# Battery_Gate_Driver.net
KiCad netlist of a schematic drawn in Altium Designer
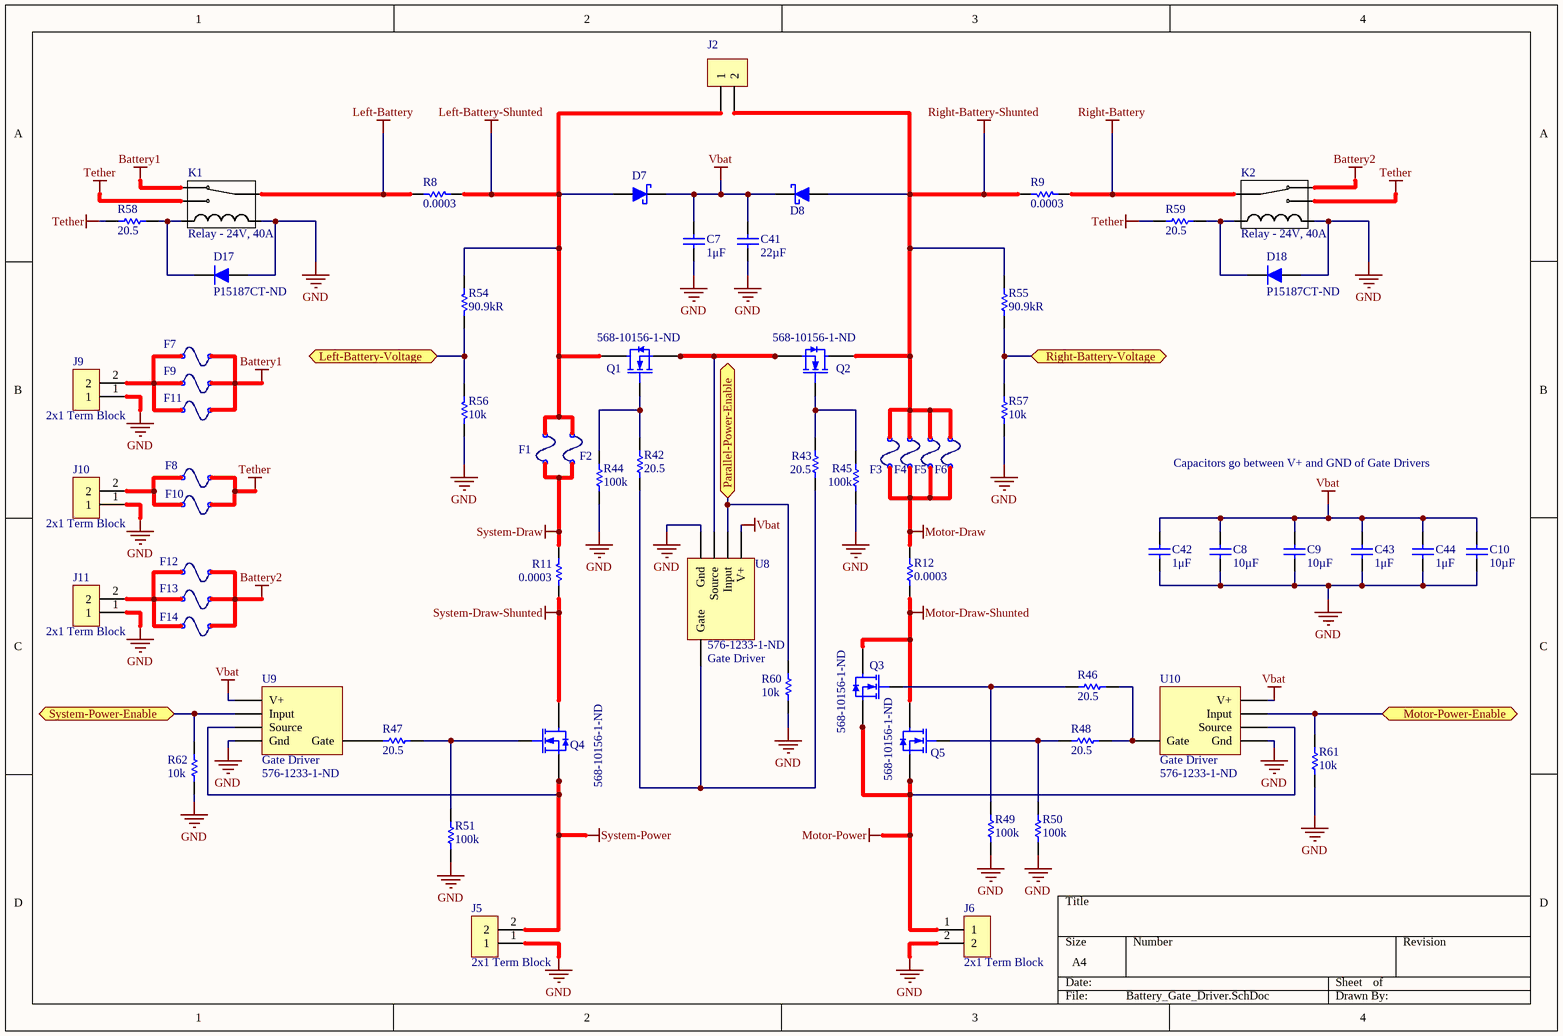
[diagram p0: Battery_Gate_Driver.SchDoc]

(export (version "E")
  (design (tool "Eeschema 10.0.6"))
  (components
    (comp (ref "C7")
      (value "1μF")
      (footprint "CAPC1608N(0603\")")
      (description "Capacitor, Ceramic, 50V, +/- 10%, 0603 SMD, X5R")
      (fields (field (name "CREATED BY") "Lyden Smith"))
      (libsource (lib "AUVic_Integrated_Library_Capacitors") (part "1uF 50V 0603 SMD, Ceramic"))
    )
    (comp (ref "C8")
      (value "10µF")
      (footprint "CAPC3216N(1206\")")
      (description "Capacitor, Ceramic, 50V, +/- 10%, 1206 SMD, X5R")
      (fields (field (name "PUBLISHER") "AUVic"))
      (libsource (lib "AUVic_Integrated_Library_Capacitors") (part "10uF 50V 1206 SMD, Ceramic"))
    )
    (comp (ref "C9")
      (value "10µF")
      (footprint "CAPC3216N(1206\")")
      (description "Capacitor, Ceramic, 50V, +/- 10%, 1206 SMD, X5R")
      (fields (field (name "PUBLISHER") "AUVic"))
      (libsource (lib "AUVic_Integrated_Library_Capacitors") (part "10uF 50V 1206 SMD, Ceramic"))
    )
    (comp (ref "C10")
      (value "10µF")
      (footprint "CAPC3216N(1206\")")
      (description "Capacitor, Ceramic, 50V, +/- 10%, 1206 SMD, X5R")
      (fields (field (name "PUBLISHER") "AUVic"))
      (libsource (lib "AUVic_Integrated_Library_Capacitors") (part "10uF 50V 1206 SMD, Ceramic"))
    )
    (comp (ref "C41")
      (value "22µF")
      (footprint "CAPC2012N(0805\")")
      (description "Capacitor, Ceramic, 35V, +/- 20%, 0805 SMD, X5R")
      (fields (field (name "PUBLISHER") "AUVic"))
      (libsource (lib "AUVic_Integrated_Library_Capacitors") (part "22uF 35V 0805 SMD, Ceramic"))
    )
    (comp (ref "C42")
      (value "1μF")
      (footprint "CAPC1608N(0603\")")
      (description "Capacitor, Ceramic, 50V, +/- 10%, 0603 SMD, X5R")
      (fields (field (name "CREATED BY") "Lyden Smith"))
      (libsource (lib "AUVic_Integrated_Library_Capacitors") (part "1uF 50V 0603 SMD, Ceramic"))
    )
    (comp (ref "C43")
      (value "1μF")
      (footprint "CAPC1608N(0603\")")
      (description "Capacitor, Ceramic, 50V, +/- 10%, 0603 SMD, X5R")
      (fields (field (name "CREATED BY") "Lyden Smith"))
      (libsource (lib "AUVic_Integrated_Library_Capacitors") (part "1uF 50V 0603 SMD, Ceramic"))
    )
    (comp (ref "C44")
      (value "1μF")
      (footprint "CAPC1608N(0603\")")
      (description "Capacitor, Ceramic, 50V, +/- 10%, 0603 SMD, X5R")
      (fields (field (name "CREATED BY") "Lyden Smith"))
      (libsource (lib "AUVic_Integrated_Library_Capacitors") (part "1uF 50V 0603 SMD, Ceramic"))
    )
    (comp (ref "D7")
      (value "CUS08F30H3FCT-ND")
      (footprint "SC-76")
      (description "Diode, Schottky, 30V, 800mA")
      (fields (field (name "CREATED BY") "Andy Bates") (field (name "PUBLISHER") "AUVic"))
      (libsource (lib "AUVic_Integrated_Library_Diodes") (part "CUS08F30H3FCT-ND"))
    )
    (comp (ref "D8")
      (value "CUS08F30H3FCT-ND")
      (footprint "SC-76")
      (description "Diode, Schottky, 30V, 800mA")
      (fields (field (name "CREATED BY") "Andy Bates") (field (name "PUBLISHER") "AUVic"))
      (libsource (lib "AUVic_Integrated_Library_Diodes") (part "CUS08F30H3FCT-ND"))
    )
    (comp (ref "D17")
      (value "DA2S10400L, SOD323F / SC-90")
      (footprint "SODFL535X110-2N")
      (fields
        (field (name "SUPPLIER PART NUMBER 1") "P15187CT-ND")
        (field (name "CREATED BY") "Andy Bates")
        (field (name "PUBLISHER") "AUVic")
      )
      (libsource (lib "AUVic_Integrated_Library_Diodes") (part "DA2S10400L, SOD323F / SC-90"))
    )
    (comp (ref "D18")
      (value "DA2S10400L, SOD323F / SC-90")
      (footprint "SODFL535X110-2N")
      (fields
        (field (name "SUPPLIER PART NUMBER 1") "P15187CT-ND")
        (field (name "CREATED BY") "Andy Bates")
        (field (name "PUBLISHER") "AUVic")
      )
      (libsource (lib "AUVic_Integrated_Library_Diodes") (part "DA2S10400L, SOD323F / SC-90"))
    )
    (comp (ref "F1")
      (value "MINI")
      (footprint "MINI BLADE FUSEHOLDER")
      (description "Blade Fuse Holder, 30A")
      (fields (field (name "CREATED BY") "Lyden Smith"))
      (libsource (lib "AUVic_Integrated_Library_Fuses") (part "MINI, ATC, ATO, etc. Blade Fuse"))
    )
    (comp (ref "F2")
      (value "MINI")
      (footprint "MINI BLADE FUSEHOLDER")
      (description "Blade Fuse Holder, 30A")
      (fields (field (name "CREATED BY") "Lyden Smith"))
      (libsource (lib "AUVic_Integrated_Library_Fuses") (part "MINI, ATC, ATO, etc. Blade Fuse"))
    )
    (comp (ref "F3")
      (value "MINI")
      (footprint "MINI BLADE FUSEHOLDER")
      (description "Blade Fuse Holder, 30A")
      (fields (field (name "CREATED BY") "Lyden Smith"))
      (libsource (lib "AUVic_Integrated_Library_Fuses") (part "MINI, ATC, ATO, etc. Blade Fuse"))
    )
    (comp (ref "F4")
      (value "MINI")
      (footprint "MINI BLADE FUSEHOLDER")
      (description "Blade Fuse Holder, 30A")
      (fields (field (name "CREATED BY") "Lyden Smith"))
      (libsource (lib "AUVic_Integrated_Library_Fuses") (part "MINI, ATC, ATO, etc. Blade Fuse"))
    )
    (comp (ref "F5")
      (value "MINI")
      (footprint "MINI BLADE FUSEHOLDER")
      (description "Blade Fuse Holder, 30A")
      (fields (field (name "CREATED BY") "Lyden Smith"))
      (libsource (lib "AUVic_Integrated_Library_Fuses") (part "MINI, ATC, ATO, etc. Blade Fuse"))
    )
    (comp (ref "F6")
      (value "MINI")
      (footprint "MINI BLADE FUSEHOLDER")
      (description "Blade Fuse Holder, 30A")
      (fields (field (name "CREATED BY") "Lyden Smith"))
      (libsource (lib "AUVic_Integrated_Library_Fuses") (part "MINI, ATC, ATO, etc. Blade Fuse"))
    )
    (comp (ref "F7")
      (value "MINI")
      (footprint "MINI BLADE FUSEHOLDER")
      (description "Blade Fuse Holder, 30A")
      (fields (field (name "CREATED BY") "Lyden Smith"))
      (libsource (lib "AUVic_Integrated_Library_Fuses") (part "MINI, ATC, ATO, etc. Blade Fuse"))
    )
    (comp (ref "F8")
      (value "MINI")
      (footprint "MINI BLADE FUSEHOLDER")
      (description "Blade Fuse Holder, 30A")
      (fields (field (name "CREATED BY") "Lyden Smith"))
      (libsource (lib "AUVic_Integrated_Library_Fuses") (part "MINI, ATC, ATO, etc. Blade Fuse"))
    )
    (comp (ref "F9")
      (value "MINI")
      (footprint "MINI BLADE FUSEHOLDER")
      (description "Blade Fuse Holder, 30A")
      (fields (field (name "CREATED BY") "Lyden Smith"))
      (libsource (lib "AUVic_Integrated_Library_Fuses") (part "MINI, ATC, ATO, etc. Blade Fuse"))
    )
    (comp (ref "F10")
      (value "MINI")
      (footprint "MINI BLADE FUSEHOLDER")
      (description "Blade Fuse Holder, 30A")
      (fields (field (name "CREATED BY") "Lyden Smith"))
      (libsource (lib "AUVic_Integrated_Library_Fuses") (part "MINI, ATC, ATO, etc. Blade Fuse"))
    )
    (comp (ref "F11")
      (value "MINI")
      (footprint "MINI BLADE FUSEHOLDER")
      (description "Blade Fuse Holder, 30A")
      (fields (field (name "CREATED BY") "Lyden Smith"))
      (libsource (lib "AUVic_Integrated_Library_Fuses") (part "MINI, ATC, ATO, etc. Blade Fuse"))
    )
    (comp (ref "F12")
      (value "MINI")
      (footprint "MINI BLADE FUSEHOLDER")
      (description "Blade Fuse Holder, 30A")
      (fields (field (name "CREATED BY") "Lyden Smith"))
      (libsource (lib "AUVic_Integrated_Library_Fuses") (part "MINI, ATC, ATO, etc. Blade Fuse"))
    )
    (comp (ref "F13")
      (value "MINI")
      (footprint "MINI BLADE FUSEHOLDER")
      (description "Blade Fuse Holder, 30A")
      (fields (field (name "CREATED BY") "Lyden Smith"))
      (libsource (lib "AUVic_Integrated_Library_Fuses") (part "MINI, ATC, ATO, etc. Blade Fuse"))
    )
    (comp (ref "F14")
      (value "MINI")
      (footprint "MINI BLADE FUSEHOLDER")
      (description "Blade Fuse Holder, 30A")
      (fields (field (name "CREATED BY") "Lyden Smith"))
      (libsource (lib "AUVic_Integrated_Library_Fuses") (part "MINI, ATC, ATO, etc. Blade Fuse"))
    )
    (comp (ref "J2")
      (value "12AWG Wire Bridge")
      (footprint "12AWG Wire Bridge")
      (fields (field (name "CREATED BY") "Lyden Smith"))
      (libsource (lib "AUVic_Integrated_Library_Connectors") (part "12AWG Wire Bridge"))
    )
    (comp (ref "J5")
      (value "2x1 Term Block")
      (footprint "2x1 Terminal Blocks EM2929")
      (fields (field (name "MADE BY") "Lyden Smith"))
      (libsource (lib "AUVic_Integrated_Library_Connectors") (part "2x1 Terminal Block, 65A, 6-20AWG"))
    )
    (comp (ref "J6")
      (value "2x1 Term Block")
      (footprint "2x1 Terminal Blocks EM2929")
      (fields (field (name "MADE BY") "Lyden Smith"))
      (libsource (lib "") (part "2x1 Terminal Block, 65A, 6-20AWG_1"))
    )
    (comp (ref "J9")
      (value "2x1 Term Block")
      (footprint "2x1 Terminal Blocks EM2929")
      (fields (field (name "MADE BY") "Lyden Smith"))
      (libsource (lib "AUVic_Integrated_Library_Connectors") (part "2x1 Terminal Block, 65A, 6-20AWG"))
    )
    (comp (ref "J10")
      (value "2x1 Term Block")
      (footprint "2x1 Terminal Blocks EM2929")
      (fields (field (name "MADE BY") "Lyden Smith"))
      (libsource (lib "AUVic_Integrated_Library_Connectors") (part "2x1 Terminal Block, 65A, 6-20AWG"))
    )
    (comp (ref "J11")
      (value "2x1 Term Block")
      (footprint "2x1 Terminal Blocks EM2929")
      (fields (field (name "MADE BY") "Lyden Smith"))
      (libsource (lib "AUVic_Integrated_Library_Connectors") (part "2x1 Terminal Block, 65A, 6-20AWG"))
    )
    (comp (ref "K1")
      (value "Relay - 24V, 40A")
      (footprint "1432871-1 Relay Footprint")
      (description "Relay, 1 Form C, SPDT, 24V, 40A")
      (libsource (lib "") (part "Relay, 1 Form C, SPDT, 24V, 40A_1"))
    )
    (comp (ref "K2")
      (value "Relay - 24V, 40A")
      (footprint "1432871-1 Relay Footprint")
      (description "Relay, 1 Form C, SPDT, 24V, 40A")
      (libsource (lib "AUVic_Integrated_Library_Relays") (part "Relay, 1 Form C, SPDT, 24V, 40A"))
    )
    (comp (ref "Q1")
      (value "MOSFET N-Channel, 40V, 100A, 272W")
      (footprint "LFPAK-PowerSO8")
      (description "MOSFET N-Channel, 40V, 100A, 272W, Enh-Mode")
      (fields
        (field (name "MFG") "NXP Semiconductors")
        (field (name "SUPPLIER PART NUMBER 1") "568-10156-1-ND")
        (field (name "CREATED BY") "Ashwin Sira")
        (field (name "PUBLISHER") "AUVic")
        (field (name "REVIEWED_BY") "Ashwin Sira")
      )
      (libsource (lib "AUVic_Integrated_Library_Transistors") (part "MOSFET N-Channel, 40V, 100A, 272W"))
    )
    (comp (ref "Q2")
      (value "MOSFET N-Channel, 40V, 100A, 272W")
      (footprint "LFPAK-PowerSO8")
      (description "MOSFET N-Channel, 40V, 100A, 272W, Enh-Mode")
      (fields
        (field (name "MFG") "NXP Semiconductors")
        (field (name "SUPPLIER PART NUMBER 1") "568-10156-1-ND")
        (field (name "CREATED BY") "Ashwin Sira")
        (field (name "PUBLISHER") "AUVic")
        (field (name "REVIEWED_BY") "Ashwin Sira")
      )
      (libsource (lib "AUVic_Integrated_Library_Transistors") (part "MOSFET N-Channel, 40V, 100A, 272W"))
    )
    (comp (ref "Q3")
      (value "MOSFET N-Channel, 40V, 100A, 272W")
      (footprint "LFPAK-PowerSO8")
      (description "MOSFET N-Channel, 40V, 100A, 272W, Enh-Mode")
      (fields
        (field (name "MFG") "NXP Semiconductors")
        (field (name "SUPPLIER PART NUMBER 1") "568-10156-1-ND")
        (field (name "CREATED BY") "Ashwin Sira")
        (field (name "PUBLISHER") "AUVic")
        (field (name "REVIEWED_BY") "Ashwin Sira")
      )
      (libsource (lib "AUVic_Integrated_Library_Transistors") (part "MOSFET N-Channel, 40V, 100A, 272W"))
    )
    (comp (ref "Q4")
      (value "MOSFET N-Channel, 40V, 100A, 272W")
      (footprint "LFPAK-PowerSO8")
      (description "MOSFET N-Channel, 40V, 100A, 272W, Enh-Mode")
      (fields
        (field (name "MFG") "NXP Semiconductors")
        (field (name "SUPPLIER PART NUMBER 1") "568-10156-1-ND")
        (field (name "CREATED BY") "Ashwin Sira")
        (field (name "PUBLISHER") "AUVic")
        (field (name "REVIEWED_BY") "Ashwin Sira")
      )
      (libsource (lib "AUVic_Integrated_Library_Transistors") (part "MOSFET N-Channel, 40V, 100A, 272W"))
    )
    (comp (ref "Q5")
      (value "MOSFET N-Channel, 40V, 100A, 272W")
      (footprint "LFPAK-PowerSO8")
      (description "MOSFET N-Channel, 40V, 100A, 272W, Enh-Mode")
      (fields
        (field (name "MFG") "NXP Semiconductors")
        (field (name "SUPPLIER PART NUMBER 1") "568-10156-1-ND")
        (field (name "CREATED BY") "Ashwin Sira")
        (field (name "PUBLISHER") "AUVic")
        (field (name "REVIEWED_BY") "Ashwin Sira")
      )
      (libsource (lib "AUVic_Integrated_Library_Transistors") (part "MOSFET N-Channel, 40V, 100A, 272W"))
    )
    (comp (ref "R8")
      (value "0.0003")
      (footprint "RESC6332N(2512\")")
      (description "0.0003R, 1%, 3W, 2512 SMD")
      (fields (field (name "MADE BY") "Ashwin Sira"))
      (libsource (lib "AUVic_Integrated_Library_Resistors") (part "0.0003R, 1%, 3W, 2512 SMD"))
    )
    (comp (ref "R9")
      (value "0.0003")
      (footprint "RESC6332N(2512\")")
      (description "0.0003R, 1%, 3W, 2512 SMD")
      (fields (field (name "MADE BY") "Ashwin Sira"))
      (libsource (lib "AUVic_Integrated_Library_Resistors") (part "0.0003R, 1%, 3W, 2512 SMD"))
    )
    (comp (ref "R11")
      (value "0.0003")
      (footprint "RESC6332N(2512\")")
      (description "0.0003R, 1%, 3W, 2512 SMD")
      (fields (field (name "MADE BY") "Ashwin Sira"))
      (libsource (lib "AUVic_Integrated_Library_Resistors") (part "0.0003R, 1%, 3W, 2512 SMD"))
    )
    (comp (ref "R12")
      (value "0.0003")
      (footprint "RESC6332N(2512\")")
      (description "0.0003R, 1%, 3W, 2512 SMD")
      (fields (field (name "MADE BY") "Ashwin Sira"))
      (libsource (lib "AUVic_Integrated_Library_Resistors") (part "0.0003R, 1%, 3W, 2512 SMD"))
    )
    (comp (ref "R42")
      (value "20.5")
      (footprint "RESC1608N(0603\")")
      (description "20.5 Ohm, 1%, 1/10W , 0603, SMD")
      (fields (field (name "CREATED BY") "Gabriel Green") (field (name "PUBLISHER") "AUVic"))
      (libsource (lib "AUVic_Integrated_Library_Resistors") (part "20.5 Ohm, 1%, 1/10W , 0603, SMD"))
    )
    (comp (ref "R43")
      (value "20.5")
      (footprint "RESC1608N(0603\")")
      (description "20.5 Ohm, 1%, 1/10W , 0603, SMD")
      (fields (field (name "CREATED BY") "Gabriel Green") (field (name "PUBLISHER") "AUVic"))
      (libsource (lib "AUVic_Integrated_Library_Resistors") (part "20.5 Ohm, 1%, 1/10W , 0603, SMD"))
    )
    (comp (ref "R44")
      (value "100k")
      (footprint "RESC2012N(0805\")")
      (description "100kR, 1%, 1/4W, 0805 SMD")
      (fields (field (name "MADE BY") "Ashwin Sira"))
      (libsource (lib "AUVic_Integrated_Library_Resistors") (part "100kR, 1%, 1/4W, 0805 SMD"))
    )
    (comp (ref "R45")
      (value "100k")
      (footprint "RESC2012N(0805\")")
      (description "100kR, 1%, 1/4W, 0805 SMD")
      (fields (field (name "MADE BY") "Ashwin Sira"))
      (libsource (lib "AUVic_Integrated_Library_Resistors") (part "100kR, 1%, 1/4W, 0805 SMD"))
    )
    (comp (ref "R46")
      (value "20.5")
      (footprint "RESC1608N(0603\")")
      (description "20.5 Ohm, 1%, 1/10W , 0603, SMD")
      (fields (field (name "CREATED BY") "Gabriel Green") (field (name "PUBLISHER") "AUVic"))
      (libsource (lib "AUVic_Integrated_Library_Resistors") (part "20.5 Ohm, 1%, 1/10W , 0603, SMD"))
    )
    (comp (ref "R47")
      (value "20.5")
      (footprint "RESC1608N(0603\")")
      (description "20.5 Ohm, 1%, 1/10W , 0603, SMD")
      (fields (field (name "CREATED BY") "Gabriel Green") (field (name "PUBLISHER") "AUVic"))
      (libsource (lib "AUVic_Integrated_Library_Resistors") (part "20.5 Ohm, 1%, 1/10W , 0603, SMD"))
    )
    (comp (ref "R48")
      (value "20.5")
      (footprint "RESC1608N(0603\")")
      (description "20.5 Ohm, 1%, 1/10W , 0603, SMD")
      (fields (field (name "CREATED BY") "Gabriel Green") (field (name "PUBLISHER") "AUVic"))
      (libsource (lib "AUVic_Integrated_Library_Resistors") (part "20.5 Ohm, 1%, 1/10W , 0603, SMD"))
    )
    (comp (ref "R49")
      (value "100k")
      (footprint "RESC2012N(0805\")")
      (description "100kR, 1%, 1/4W, 0805 SMD")
      (fields (field (name "MADE BY") "Ashwin Sira"))
      (libsource (lib "AUVic_Integrated_Library_Resistors") (part "100kR, 1%, 1/4W, 0805 SMD"))
    )
    (comp (ref "R50")
      (value "100k")
      (footprint "RESC2012N(0805\")")
      (description "100kR, 1%, 1/4W, 0805 SMD")
      (fields (field (name "MADE BY") "Ashwin Sira"))
      (libsource (lib "AUVic_Integrated_Library_Resistors") (part "100kR, 1%, 1/4W, 0805 SMD"))
    )
    (comp (ref "R51")
      (value "100k")
      (footprint "RESC2012N(0805\")")
      (description "100kR, 1%, 1/4W, 0805 SMD")
      (fields (field (name "MADE BY") "Ashwin Sira"))
      (libsource (lib "AUVic_Integrated_Library_Resistors") (part "100kR, 1%, 1/4W, 0805 SMD"))
    )
    (comp (ref "R54")
      (value "90.9kR")
      (footprint "RESC1608N(0603\")")
      (description "90.9k, 1%, 1/10W, 0603, SMD")
      (fields (field (name "CREATED BY") "Andy Bates") (field (name "PUBLISHER") "AUVic"))
      (libsource (lib "AUVic_Integrated_Library_Resistors") (part "90.9k, 1%, 1/10W, 0603, SMD"))
    )
    (comp (ref "R55")
      (value "90.9kR")
      (footprint "RESC1608N(0603\")")
      (description "90.9k, 1%, 1/10W, 0603, SMD")
      (fields (field (name "CREATED BY") "Andy Bates") (field (name "PUBLISHER") "AUVic"))
      (libsource (lib "AUVic_Integrated_Library_Resistors") (part "90.9k, 1%, 1/10W, 0603, SMD"))
    )
    (comp (ref "R56")
      (value "10k")
      (footprint "RESC1608N(0603\")")
      (description "10kR, 1%, 1/10W, 0603 SMD")
      (fields (field (name "MADE BY") "Ashwin Sira"))
      (libsource (lib "AUVic_Integrated_Library_Resistors") (part "10kR, 1%, 1/10W, 0603 SMD"))
    )
    (comp (ref "R57")
      (value "10k")
      (footprint "RESC1608N(0603\")")
      (description "10kR, 1%, 1/10W, 0603 SMD")
      (fields (field (name "MADE BY") "Ashwin Sira"))
      (libsource (lib "AUVic_Integrated_Library_Resistors") (part "10kR, 1%, 1/10W, 0603 SMD"))
    )
    (comp (ref "R58")
      (value "20.5")
      (footprint "RESC1608N(0603\")")
      (description "20.5 Ohm, 1%, 1/10W , 0603, SMD")
      (fields (field (name "CREATED BY") "Gabriel Green") (field (name "PUBLISHER") "AUVic"))
      (libsource (lib "AUVic_Integrated_Library_Resistors") (part "20.5 Ohm, 1%, 1/10W , 0603, SMD"))
    )
    (comp (ref "R59")
      (value "20.5")
      (footprint "RESC1608N(0603\")")
      (description "20.5 Ohm, 1%, 1/10W , 0603, SMD")
      (fields (field (name "CREATED BY") "Gabriel Green") (field (name "PUBLISHER") "AUVic"))
      (libsource (lib "AUVic_Integrated_Library_Resistors") (part "20.5 Ohm, 1%, 1/10W , 0603, SMD"))
    )
    (comp (ref "R60")
      (value "10k")
      (footprint "RESC1608N(0603\")")
      (description "10kR, 1%, 1/10W, 0603 SMD")
      (fields (field (name "MADE BY") "Ashwin Sira"))
      (libsource (lib "AUVic_Integrated_Library_Resistors") (part "10kR, 1%, 1/10W, 0603 SMD"))
    )
    (comp (ref "R61")
      (value "10k")
      (footprint "RESC1608N(0603\")")
      (description "10kR, 1%, 1/10W, 0603 SMD")
      (fields (field (name "MADE BY") "Ashwin Sira"))
      (libsource (lib "AUVic_Integrated_Library_Resistors") (part "10kR, 1%, 1/10W, 0603 SMD"))
    )
    (comp (ref "R62")
      (value "10k")
      (footprint "RESC1608N(0603\")")
      (description "10kR, 1%, 1/10W, 0603 SMD")
      (fields (field (name "MADE BY") "Ashwin Sira"))
      (libsource (lib "AUVic_Integrated_Library_Resistors") (part "10kR, 1%, 1/10W, 0603 SMD"))
    )
    (comp (ref "U8")
      (value "Gate Driver")
      (footprint "SOC 8")
      (fields (field (name "SUPPLIER PART NUMBER 1") "576-1233-1-ND"))
      (libsource (lib "AUVic_Integrated_Library_Gate_Drivers") (part "Gate Driver TTL Logic 3 - 30V"))
    )
    (comp (ref "U9")
      (value "Gate Driver")
      (footprint "SOC 8")
      (fields (field (name "SUPPLIER PART NUMBER 1") "576-1233-1-ND"))
      (libsource (lib "") (part "Gate Driver TTL Logic 3 - 30V_1"))
    )
    (comp (ref "U10")
      (value "Gate Driver")
      (footprint "SOC 8")
      (fields (field (name "SUPPLIER PART NUMBER 1") "576-1233-1-ND"))
      (libsource (lib "AUVic_Integrated_Library_Gate_Drivers") (part "Gate Driver TTL Logic 3 - 30V"))
    )
  )
  (nets
    (net (code "1") (name "/Left-Battery-Voltage") (class "Default")
      (node (ref "R54") (pin "2") (pinfunction "2_2") (pintype "passive"))
      (node (ref "R56") (pin "1") (pinfunction "1_1") (pintype "passive"))
    )
    (net (code "2") (name "/Motor-Power-Enable") (class "Default")
      (node (ref "R61") (pin "1") (pinfunction "1_1") (pintype "passive"))
      (node (ref "U10") (pin "2") (pinfunction "Input_2") (pintype "passive"))
    )
    (net (code "3") (name "/Parallel-Power-Enable") (class "Default")
      (node (ref "R60") (pin "1") (pinfunction "1_1") (pintype "passive"))
      (node (ref "U8") (pin "2") (pinfunction "Input_2") (pintype "passive"))
    )
    (net (code "4") (name "/Right-Battery-Voltage") (class "Default")
      (node (ref "R55") (pin "2") (pinfunction "2_2") (pintype "passive"))
      (node (ref "R57") (pin "1") (pinfunction "1_1") (pintype "passive"))
    )
    (net (code "5") (name "/System-Power-Enable") (class "Default")
      (node (ref "R62") (pin "1") (pinfunction "1_1") (pintype "passive"))
      (node (ref "U9") (pin "2") (pinfunction "Input_2") (pintype "passive"))
    )
    (net (code "6") (name "Battery1") (class "Default")
      (node (ref "F11") (pin "2") (pinfunction "2_2") (pintype "passive"))
      (node (ref "F7") (pin "2") (pinfunction "2_2") (pintype "passive"))
      (node (ref "F9") (pin "2") (pinfunction "2_2") (pintype "passive"))
      (node (ref "K1") (pin "87a") (pinfunction "87a_87a") (pintype "passive"))
    )
    (net (code "7") (name "Battery2") (class "Default")
      (node (ref "F12") (pin "2") (pinfunction "2_2") (pintype "passive"))
      (node (ref "F13") (pin "2") (pinfunction "2_2") (pintype "passive"))
      (node (ref "F14") (pin "2") (pinfunction "2_2") (pintype "passive"))
      (node (ref "K2") (pin "87a") (pinfunction "87a_87a") (pintype "passive"))
    )
    (net (code "8") (name "GND") (class "Default")
      (node (ref "C10") (pin "1") (pinfunction "Anode_1") (pintype "passive"))
      (node (ref "C41") (pin "1") (pinfunction "Anode_1") (pintype "passive"))
      (node (ref "C42") (pin "1") (pinfunction "Anode_1") (pintype "passive"))
      (node (ref "C43") (pin "1") (pinfunction "Anode_1") (pintype "passive"))
      (node (ref "C44") (pin "1") (pinfunction "Anode_1") (pintype "passive"))
      (node (ref "C7") (pin "1") (pinfunction "Anode_1") (pintype "passive"))
      (node (ref "C8") (pin "1") (pinfunction "Anode_1") (pintype "passive"))
      (node (ref "C9") (pin "1") (pinfunction "Anode_1") (pintype "passive"))
      (node (ref "D17") (pin "1") (pinfunction "Anode_1") (pintype "passive"))
      (node (ref "D18") (pin "1") (pinfunction "Anode_1") (pintype "passive"))
      (node (ref "J10") (pin "1") (pinfunction "1_1") (pintype "passive"))
      (node (ref "J11") (pin "1") (pinfunction "1_1") (pintype "passive"))
      (node (ref "J5") (pin "1") (pinfunction "1_1") (pintype "passive"))
      (node (ref "J6") (pin "2") (pinfunction "2_2") (pintype "passive"))
      (node (ref "J9") (pin "1") (pinfunction "1_1") (pintype "passive"))
      (node (ref "K1") (pin "85") (pinfunction "85_85") (pintype "passive"))
      (node (ref "K2") (pin "86") (pinfunction "86_86") (pintype "passive"))
      (node (ref "R44") (pin "1") (pinfunction "1_1") (pintype "passive"))
      (node (ref "R45") (pin "1") (pinfunction "1_1") (pintype "passive"))
      (node (ref "R49") (pin "1") (pinfunction "1_1") (pintype "passive"))
      (node (ref "R50") (pin "1") (pinfunction "1_1") (pintype "passive"))
      (node (ref "R51") (pin "1") (pinfunction "1_1") (pintype "passive"))
      (node (ref "R56") (pin "2") (pinfunction "2_2") (pintype "passive"))
      (node (ref "R57") (pin "2") (pinfunction "2_2") (pintype "passive"))
      (node (ref "R60") (pin "2") (pinfunction "2_2") (pintype "passive"))
      (node (ref "R61") (pin "2") (pinfunction "2_2") (pintype "passive"))
      (node (ref "R62") (pin "2") (pinfunction "2_2") (pintype "passive"))
      (node (ref "U10") (pin "4") (pinfunction "Gnd_4") (pintype "passive"))
      (node (ref "U8") (pin "4") (pinfunction "Gnd_4") (pintype "passive"))
      (node (ref "U9") (pin "4") (pinfunction "Gnd_4") (pintype "passive"))
    )
    (net (code "9") (name "Left-Battery") (class "Default")
      (node (ref "K1") (pin "30") (pinfunction "30_30") (pintype "passive"))
      (node (ref "R8") (pin "2") (pinfunction "2_2") (pintype "passive"))
    )
    (net (code "10") (name "Left-Battery-Shunted") (class "Default")
      (node (ref "D7") (pin "A") (pinfunction "Anode_A") (pintype "passive"))
      (node (ref "F1") (pin "2") (pinfunction "2_2") (pintype "passive"))
      (node (ref "F2") (pin "2") (pinfunction "2_2") (pintype "passive"))
      (node (ref "J2") (pin "1") (pinfunction "1_1") (pintype "passive"))
      (node (ref "Q1") (pin "5") (pinfunction "Drain_5") (pintype "power_in"))
      (node (ref "R54") (pin "1") (pinfunction "1_1") (pintype "passive"))
      (node (ref "R8") (pin "1") (pinfunction "1_1") (pintype "passive"))
    )
    (net (code "11") (name "Motor-Draw") (class "Default")
      (node (ref "F3") (pin "1") (pinfunction "1_1") (pintype "passive"))
      (node (ref "F4") (pin "1") (pinfunction "1_1") (pintype "passive"))
      (node (ref "F5") (pin "1") (pinfunction "1_1") (pintype "passive"))
      (node (ref "F6") (pin "1") (pinfunction "1_1") (pintype "passive"))
      (node (ref "R12") (pin "1") (pinfunction "1_1") (pintype "passive"))
    )
    (net (code "12") (name "Motor-Draw-Shunted") (class "Default")
      (node (ref "Q3") (pin "5") (pinfunction "Drain_5") (pintype "power_in"))
      (node (ref "Q5") (pin "5") (pinfunction "Drain_5") (pintype "power_in"))
      (node (ref "R12") (pin "2") (pinfunction "2_2") (pintype "passive"))
    )
    (net (code "13") (name "Motor-Power") (class "Default")
      (node (ref "J6") (pin "1") (pinfunction "1_1") (pintype "passive"))
      (node (ref "Q3") (pin "1") (pinfunction "Source_1") (pintype "power_in"))
      (node (ref "Q3") (pin "2") (pinfunction "Source_2") (pintype "power_in"))
      (node (ref "Q3") (pin "3") (pinfunction "Source_3") (pintype "power_in"))
      (node (ref "Q5") (pin "1") (pinfunction "Source_1") (pintype "power_in"))
      (node (ref "Q5") (pin "2") (pinfunction "Source_2") (pintype "power_in"))
      (node (ref "Q5") (pin "3") (pinfunction "Source_3") (pintype "power_in"))
      (node (ref "U10") (pin "3") (pinfunction "Source_3") (pintype "passive"))
    )
    (net (code "14") (name "Net-(D17-Cathode)") (class "Default")
      (node (ref "D17") (pin "2") (pinfunction "Cathode_2") (pintype "passive"))
      (node (ref "K1") (pin "86") (pinfunction "86_86") (pintype "passive"))
      (node (ref "R58") (pin "2") (pinfunction "2_2") (pintype "passive"))
    )
    (net (code "15") (name "Net-(D18-Cathode)") (class "Default")
      (node (ref "D18") (pin "2") (pinfunction "Cathode_2") (pintype "passive"))
      (node (ref "K2") (pin "85") (pinfunction "85_85") (pintype "passive"))
      (node (ref "R59") (pin "2") (pinfunction "2_2") (pintype "passive"))
    )
    (net (code "16") (name "Net-(F10-Pad1)") (class "Default")
      (node (ref "F10") (pin "1") (pinfunction "1_1") (pintype "passive"))
      (node (ref "F8") (pin "1") (pinfunction "1_1") (pintype "passive"))
      (node (ref "J10") (pin "2") (pinfunction "2_2") (pintype "passive"))
    )
    (net (code "17") (name "Net-(F11-Pad1)") (class "Default")
      (node (ref "F11") (pin "1") (pinfunction "1_1") (pintype "passive"))
      (node (ref "F7") (pin "1") (pinfunction "1_1") (pintype "passive"))
      (node (ref "F9") (pin "1") (pinfunction "1_1") (pintype "passive"))
      (node (ref "J9") (pin "2") (pinfunction "2_2") (pintype "passive"))
    )
    (net (code "18") (name "Net-(F12-Pad1)") (class "Default")
      (node (ref "F12") (pin "1") (pinfunction "1_1") (pintype "passive"))
      (node (ref "F13") (pin "1") (pinfunction "1_1") (pintype "passive"))
      (node (ref "F14") (pin "1") (pinfunction "1_1") (pintype "passive"))
      (node (ref "J11") (pin "2") (pinfunction "2_2") (pintype "passive"))
    )
    (net (code "19") (name "Net-(Q1-Gate)") (class "Default")
      (node (ref "Q1") (pin "4") (pinfunction "Gate_4") (pintype "power_in"))
      (node (ref "R42") (pin "2") (pinfunction "2_2") (pintype "passive"))
      (node (ref "R44") (pin "2") (pinfunction "2_2") (pintype "passive"))
    )
    (net (code "20") (name "Net-(Q2-Gate)") (class "Default")
      (node (ref "Q2") (pin "4") (pinfunction "Gate_4") (pintype "power_in"))
      (node (ref "R43") (pin "2") (pinfunction "2_2") (pintype "passive"))
      (node (ref "R45") (pin "2") (pinfunction "2_2") (pintype "passive"))
    )
    (net (code "21") (name "Net-(Q3-Gate)") (class "Default")
      (node (ref "Q3") (pin "4") (pinfunction "Gate_4") (pintype "power_in"))
      (node (ref "R46") (pin "2") (pinfunction "2_2") (pintype "passive"))
      (node (ref "R49") (pin "2") (pinfunction "2_2") (pintype "passive"))
    )
    (net (code "22") (name "Net-(Q4-Gate)") (class "Default")
      (node (ref "Q4") (pin "4") (pinfunction "Gate_4") (pintype "power_in"))
      (node (ref "R47") (pin "1") (pinfunction "1_1") (pintype "passive"))
      (node (ref "R51") (pin "2") (pinfunction "2_2") (pintype "passive"))
    )
    (net (code "23") (name "Net-(Q5-Gate)") (class "Default")
      (node (ref "Q5") (pin "4") (pinfunction "Gate_4") (pintype "power_in"))
      (node (ref "R48") (pin "2") (pinfunction "2_2") (pintype "passive"))
      (node (ref "R50") (pin "2") (pinfunction "2_2") (pintype "passive"))
    )
    (net (code "24") (name "Net-(U8-Gate)") (class "Default")
      (node (ref "R42") (pin "1") (pinfunction "1_1") (pintype "passive"))
      (node (ref "R43") (pin "1") (pinfunction "1_1") (pintype "passive"))
      (node (ref "U8") (pin "5") (pinfunction "Gate_5") (pintype "passive"))
    )
    (net (code "25") (name "Net-(U8-Source)") (class "Default")
      (node (ref "Q1") (pin "1") (pinfunction "Source_1") (pintype "power_in"))
      (node (ref "Q1") (pin "2") (pinfunction "Source_2") (pintype "power_in"))
      (node (ref "Q1") (pin "3") (pinfunction "Source_3") (pintype "power_in"))
      (node (ref "Q2") (pin "1") (pinfunction "Source_1") (pintype "power_in"))
      (node (ref "Q2") (pin "2") (pinfunction "Source_2") (pintype "power_in"))
      (node (ref "Q2") (pin "3") (pinfunction "Source_3") (pintype "power_in"))
      (node (ref "U8") (pin "3") (pinfunction "Source_3") (pintype "passive"))
    )
    (net (code "26") (name "Net-(U9-Gate)") (class "Default")
      (node (ref "R47") (pin "2") (pinfunction "2_2") (pintype "passive"))
      (node (ref "U9") (pin "5") (pinfunction "Gate_5") (pintype "passive"))
    )
    (net (code "27") (name "Net-(U10-Gate)") (class "Default")
      (node (ref "R46") (pin "1") (pinfunction "1_1") (pintype "passive"))
      (node (ref "R48") (pin "1") (pinfunction "1_1") (pintype "passive"))
      (node (ref "U10") (pin "5") (pinfunction "Gate_5") (pintype "passive"))
    )
    (net (code "28") (name "Right-Battery") (class "Default")
      (node (ref "K2") (pin "30") (pinfunction "30_30") (pintype "passive"))
      (node (ref "R9") (pin "1") (pinfunction "1_1") (pintype "passive"))
    )
    (net (code "29") (name "Right-Battery-Shunted") (class "Default")
      (node (ref "D8") (pin "A") (pinfunction "Anode_A") (pintype "passive"))
      (node (ref "F3") (pin "2") (pinfunction "2_2") (pintype "passive"))
      (node (ref "F4") (pin "2") (pinfunction "2_2") (pintype "passive"))
      (node (ref "F5") (pin "2") (pinfunction "2_2") (pintype "passive"))
      (node (ref "F6") (pin "2") (pinfunction "2_2") (pintype "passive"))
      (node (ref "J2") (pin "2") (pinfunction "2_2") (pintype "passive"))
      (node (ref "Q2") (pin "5") (pinfunction "Drain_5") (pintype "power_in"))
      (node (ref "R55") (pin "1") (pinfunction "1_1") (pintype "passive"))
      (node (ref "R9") (pin "2") (pinfunction "2_2") (pintype "passive"))
    )
    (net (code "30") (name "System-Draw") (class "Default")
      (node (ref "F1") (pin "1") (pinfunction "1_1") (pintype "passive"))
      (node (ref "F2") (pin "1") (pinfunction "1_1") (pintype "passive"))
      (node (ref "R11") (pin "2") (pinfunction "2_2") (pintype "passive"))
    )
    (net (code "31") (name "System-Draw-Shunted") (class "Default")
      (node (ref "Q4") (pin "5") (pinfunction "Drain_5") (pintype "power_in"))
      (node (ref "R11") (pin "1") (pinfunction "1_1") (pintype "passive"))
    )
    (net (code "32") (name "System-Power") (class "Default")
      (node (ref "J5") (pin "2") (pinfunction "2_2") (pintype "passive"))
      (node (ref "Q4") (pin "1") (pinfunction "Source_1") (pintype "power_in"))
      (node (ref "Q4") (pin "2") (pinfunction "Source_2") (pintype "power_in"))
      (node (ref "Q4") (pin "3") (pinfunction "Source_3") (pintype "power_in"))
      (node (ref "U9") (pin "3") (pinfunction "Source_3") (pintype "passive"))
    )
    (net (code "33") (name "Tether") (class "Default")
      (node (ref "F10") (pin "2") (pinfunction "2_2") (pintype "passive"))
      (node (ref "F8") (pin "2") (pinfunction "2_2") (pintype "passive"))
      (node (ref "K1") (pin "87") (pinfunction "87_87") (pintype "passive"))
      (node (ref "K2") (pin "87") (pinfunction "87_87") (pintype "passive"))
      (node (ref "R58") (pin "1") (pinfunction "1_1") (pintype "passive"))
      (node (ref "R59") (pin "1") (pinfunction "1_1") (pintype "passive"))
    )
    (net (code "34") (name "Vbat") (class "Default")
      (node (ref "C10") (pin "2") (pinfunction "Cathode_2") (pintype "passive"))
      (node (ref "C41") (pin "2") (pinfunction "Cathode_2") (pintype "passive"))
      (node (ref "C42") (pin "2") (pinfunction "Cathode_2") (pintype "passive"))
      (node (ref "C43") (pin "2") (pinfunction "Cathode_2") (pintype "passive"))
      (node (ref "C44") (pin "2") (pinfunction "Cathode_2") (pintype "passive"))
      (node (ref "C7") (pin "2") (pinfunction "Cathode_2") (pintype "passive"))
      (node (ref "C8") (pin "2") (pinfunction "Cathode_2") (pintype "passive"))
      (node (ref "C9") (pin "2") (pinfunction "Cathode_2") (pintype "passive"))
      (node (ref "D7") (pin "K") (pinfunction "Cathode_K") (pintype "passive"))
      (node (ref "D8") (pin "K") (pinfunction "Cathode_K") (pintype "passive"))
      (node (ref "U10") (pin "1") (pinfunction "V+_1") (pintype "passive"))
      (node (ref "U8") (pin "1") (pinfunction "V+_1") (pintype "passive"))
      (node (ref "U9") (pin "1") (pinfunction "V+_1") (pintype "passive"))
    )
  )
)
